# MOD-V_V10.net
KiCad netlist of a schematic drawn in EAGLE
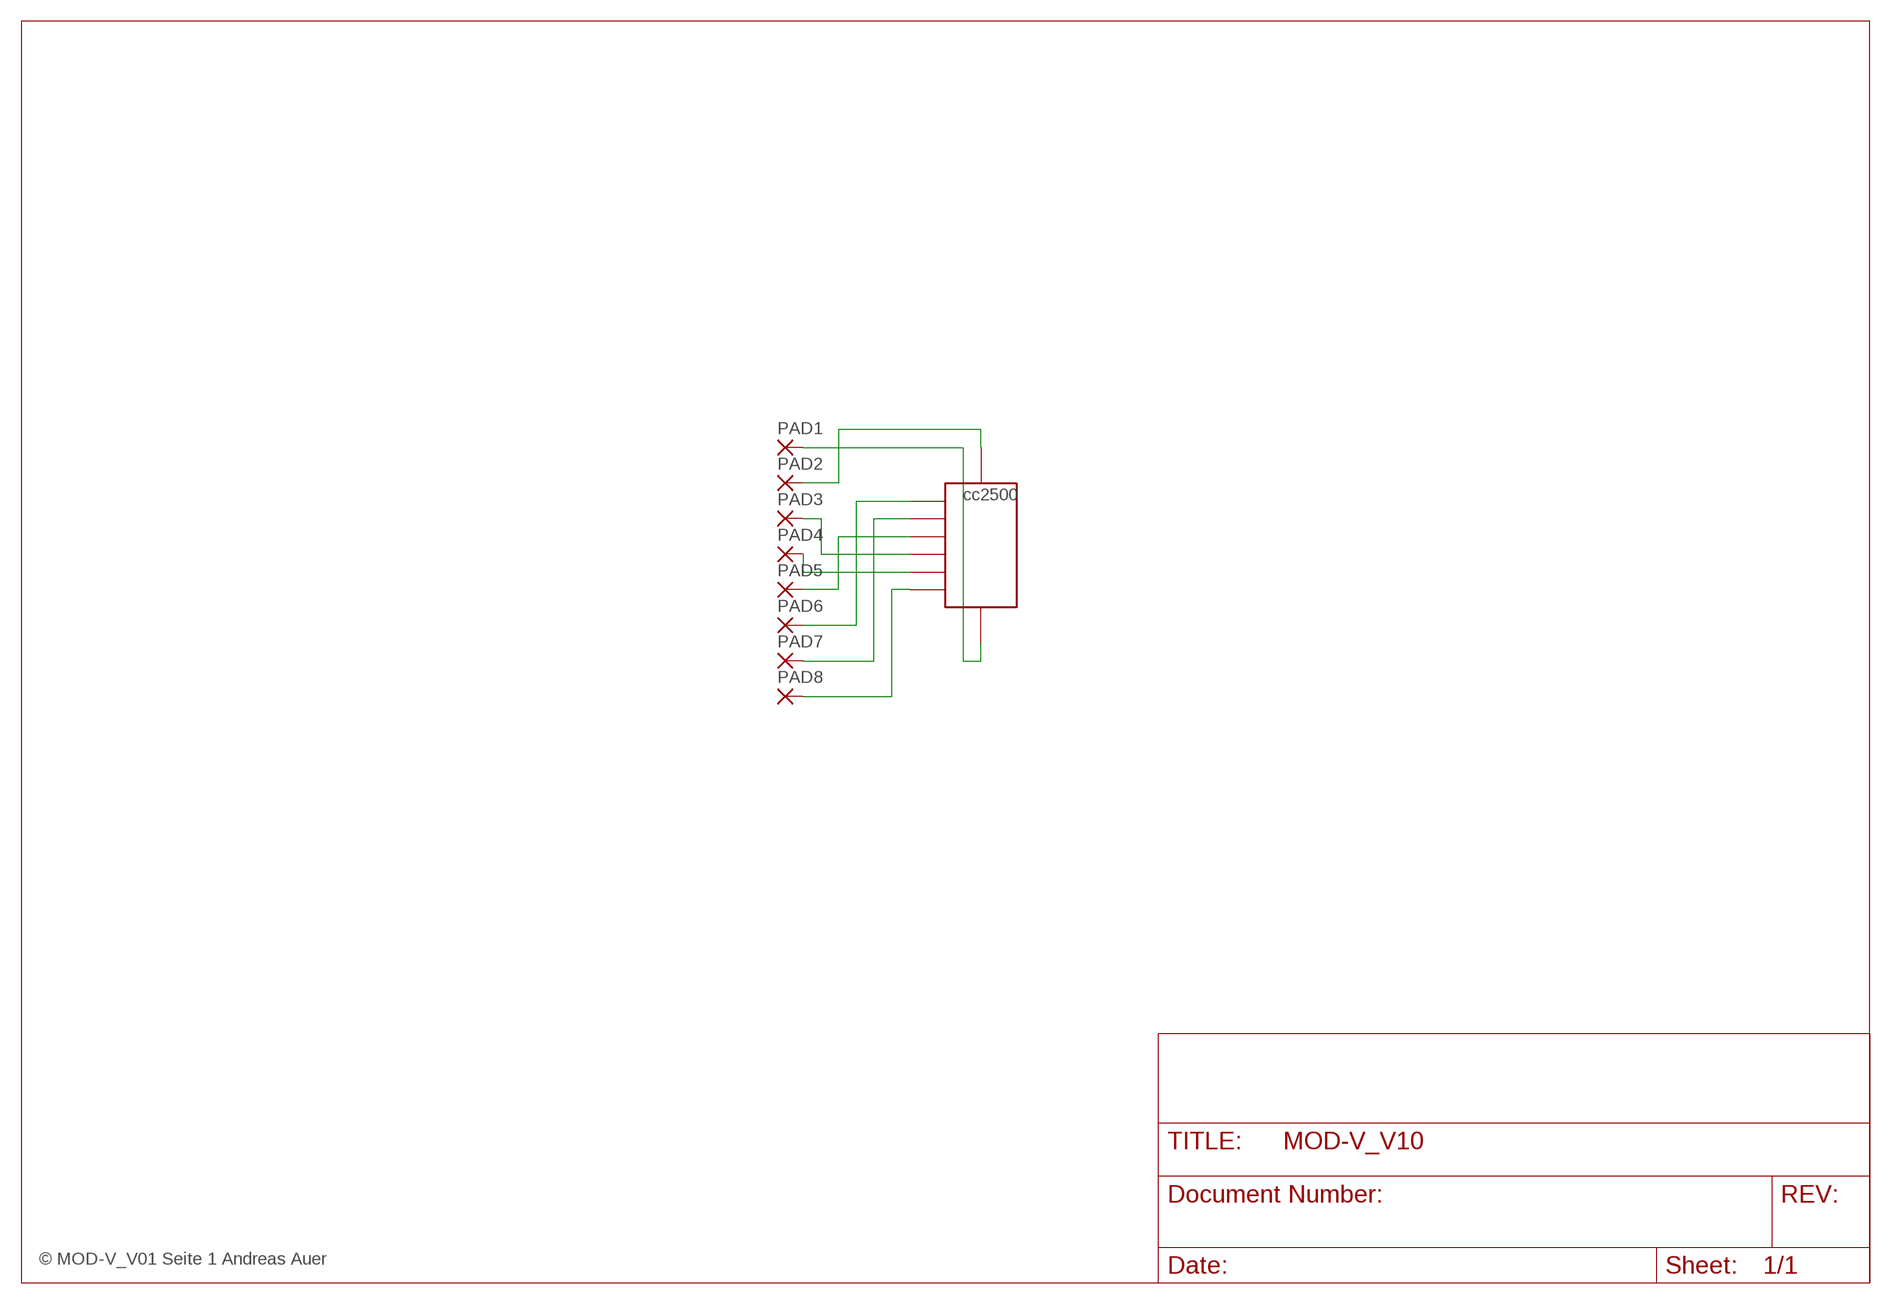
[diagram p0: schematic, sheet 1]

(export (version "E")
  (design (tool "Eeschema 10.0.6"))
  (components
    (comp (ref "IC1")
      (value "CC2500")
      (footprint "eagle-import:CC2500")
      (libsource (lib "eagle-import") (part "CC2500"))
    )
    (comp (ref "PAD1")
      (value "SMD2")
      (footprint "eagle-import:SMD1,27-2,54")
      (libsource (lib "eagle-import") (part "SMD2"))
    )
    (comp (ref "PAD2")
      (value "SMD2")
      (footprint "eagle-import:SMD1,27-2,54")
      (libsource (lib "eagle-import") (part "SMD2"))
    )
    (comp (ref "PAD3")
      (value "SMD2")
      (footprint "eagle-import:SMD1,27-2,54")
      (libsource (lib "eagle-import") (part "SMD2"))
    )
    (comp (ref "PAD4")
      (value "SMD2")
      (footprint "eagle-import:SMD1,27-2,54")
      (libsource (lib "eagle-import") (part "SMD2"))
    )
    (comp (ref "PAD5")
      (value "SMD2")
      (footprint "eagle-import:SMD1,27-2,54")
      (libsource (lib "eagle-import") (part "SMD2"))
    )
    (comp (ref "PAD6")
      (value "SMD2")
      (footprint "eagle-import:SMD1,27-2,54")
      (libsource (lib "eagle-import") (part "SMD2"))
    )
    (comp (ref "PAD7")
      (value "SMD2")
      (footprint "eagle-import:SMD1,27-2,54")
      (libsource (lib "eagle-import") (part "SMD2"))
    )
    (comp (ref "PAD8")
      (value "SMD2")
      (footprint "eagle-import:SMD1,27-2,54")
      (libsource (lib "eagle-import") (part "SMD2"))
    )
  )
  (nets
    (net (code "1") (name "Net-(PAD1-P)") (class "Default")
      (node (ref "IC1") (pin "GND") (pinfunction "GND_GND") (pintype "power_in"))
      (node (ref "PAD1") (pin "1") (pinfunction "P_1") (pintype "passive"))
    )
    (net (code "2") (name "Net-(PAD2-P)") (class "Default")
      (node (ref "IC1") (pin "+3V3") (pinfunction "+3V3_+3V3") (pintype "power_in"))
      (node (ref "PAD2") (pin "1") (pinfunction "P_1") (pintype "passive"))
    )
    (net (code "3") (name "Net-(PAD3-P)") (class "Default")
      (node (ref "IC1") (pin "MOSI") (pinfunction "MOSI_MOSI") (pintype "bidirectional"))
      (node (ref "PAD3") (pin "1") (pinfunction "P_1") (pintype "passive"))
    )
    (net (code "4") (name "Net-(PAD4-P)") (class "Default")
      (node (ref "IC1") (pin "SPSCK") (pinfunction "SPSCK_SPSCK") (pintype "bidirectional"))
      (node (ref "PAD4") (pin "1") (pinfunction "P_1") (pintype "passive"))
    )
    (net (code "5") (name "Net-(PAD5-P)") (class "Default")
      (node (ref "IC1") (pin "MISO") (pinfunction "MISO_MISO") (pintype "bidirectional"))
      (node (ref "PAD5") (pin "1") (pinfunction "P_1") (pintype "passive"))
    )
    (net (code "6") (name "Net-(PAD6-P)") (class "Default")
      (node (ref "IC1") (pin "GD0") (pinfunction "GD0_GD0") (pintype "bidirectional"))
      (node (ref "PAD6") (pin "1") (pinfunction "P_1") (pintype "passive"))
    )
    (net (code "7") (name "Net-(PAD7-P)") (class "Default")
      (node (ref "IC1") (pin "GD2") (pinfunction "GD2_GD2") (pintype "bidirectional"))
      (node (ref "PAD7") (pin "1") (pinfunction "P_1") (pintype "passive"))
    )
    (net (code "8") (name "Net-(PAD8-P)") (class "Default")
      (node (ref "IC1") (pin "CS") (pinfunction "CS_CS") (pintype "bidirectional"))
      (node (ref "PAD8") (pin "1") (pinfunction "P_1") (pintype "passive"))
    )
  )
)
